# Power_IO.net
KiCad netlist of a schematic drawn in Altium Designer
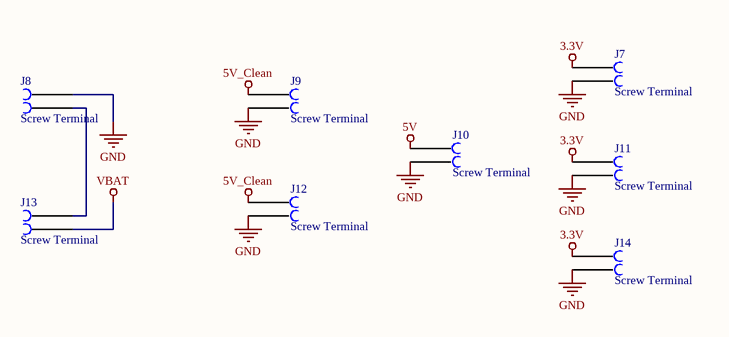
[diagram p0: Power IO.SchDoc]

(export (version "E")
  (design (tool "Eeschema 10.0.6"))
  (components
    (comp (ref "J7")
      (value "Screw Terminal")
      (footprint "Screw Terminal")
      (libsource (lib "AvionicsParts") (part "Screw Terminal"))
    )
    (comp (ref "J8")
      (value "Screw Terminal")
      (footprint "Screw Terminal")
      (libsource (lib "AvionicsParts") (part "Screw Terminal"))
    )
    (comp (ref "J9")
      (value "Screw Terminal")
      (footprint "Screw Terminal")
      (libsource (lib "AvionicsParts") (part "Screw Terminal"))
    )
    (comp (ref "J10")
      (value "Screw Terminal")
      (footprint "Screw Terminal")
      (libsource (lib "AvionicsParts") (part "Screw Terminal"))
    )
    (comp (ref "J11")
      (value "Screw Terminal")
      (footprint "Screw Terminal")
      (libsource (lib "AvionicsParts") (part "Screw Terminal"))
    )
    (comp (ref "J12")
      (value "Screw Terminal")
      (footprint "Screw Terminal")
      (libsource (lib "AvionicsParts") (part "Screw Terminal"))
    )
    (comp (ref "J13")
      (value "Screw Terminal")
      (footprint "Screw Terminal")
      (libsource (lib "AvionicsParts") (part "Screw Terminal"))
    )
    (comp (ref "J14")
      (value "Screw Terminal")
      (footprint "Screw Terminal")
      (libsource (lib "AvionicsParts") (part "Screw Terminal"))
    )
  )
  (nets
    (net (code "1") (name "3.3V") (class "Default")
      (node (ref "J11") (pin "1") (pinfunction "1_1") (pintype "passive"))
      (node (ref "J14") (pin "1") (pinfunction "1_1") (pintype "passive"))
      (node (ref "J7") (pin "1") (pinfunction "1_1") (pintype "passive"))
    )
    (net (code "2") (name "5V") (class "Default")
      (node (ref "J10") (pin "1") (pinfunction "1_1") (pintype "passive"))
    )
    (net (code "3") (name "5V_Clean") (class "Default")
      (node (ref "J12") (pin "1") (pinfunction "1_1") (pintype "passive"))
      (node (ref "J9") (pin "1") (pinfunction "1_1") (pintype "passive"))
    )
    (net (code "4") (name "GND") (class "Default")
      (node (ref "J10") (pin "2") (pinfunction "2_2") (pintype "passive"))
      (node (ref "J11") (pin "2") (pinfunction "2_2") (pintype "passive"))
      (node (ref "J12") (pin "2") (pinfunction "2_2") (pintype "passive"))
      (node (ref "J14") (pin "2") (pinfunction "2_2") (pintype "passive"))
      (node (ref "J7") (pin "2") (pinfunction "2_2") (pintype "passive"))
      (node (ref "J8") (pin "2") (pinfunction "2_2") (pintype "passive"))
      (node (ref "J9") (pin "2") (pinfunction "2_2") (pintype "passive"))
    )
    (net (code "5") (name "Net-(J13-Pad2)") (class "Default")
      (node (ref "J13") (pin "2") (pinfunction "2_2") (pintype "passive"))
      (node (ref "J8") (pin "1") (pinfunction "1_1") (pintype "passive"))
    )
    (net (code "6") (name "VBAT") (class "Default")
      (node (ref "J13") (pin "1") (pinfunction "1_1") (pintype "passive"))
    )
  )
)
